# AUDIO.net
KiCad netlist of a schematic drawn in Altium Designer
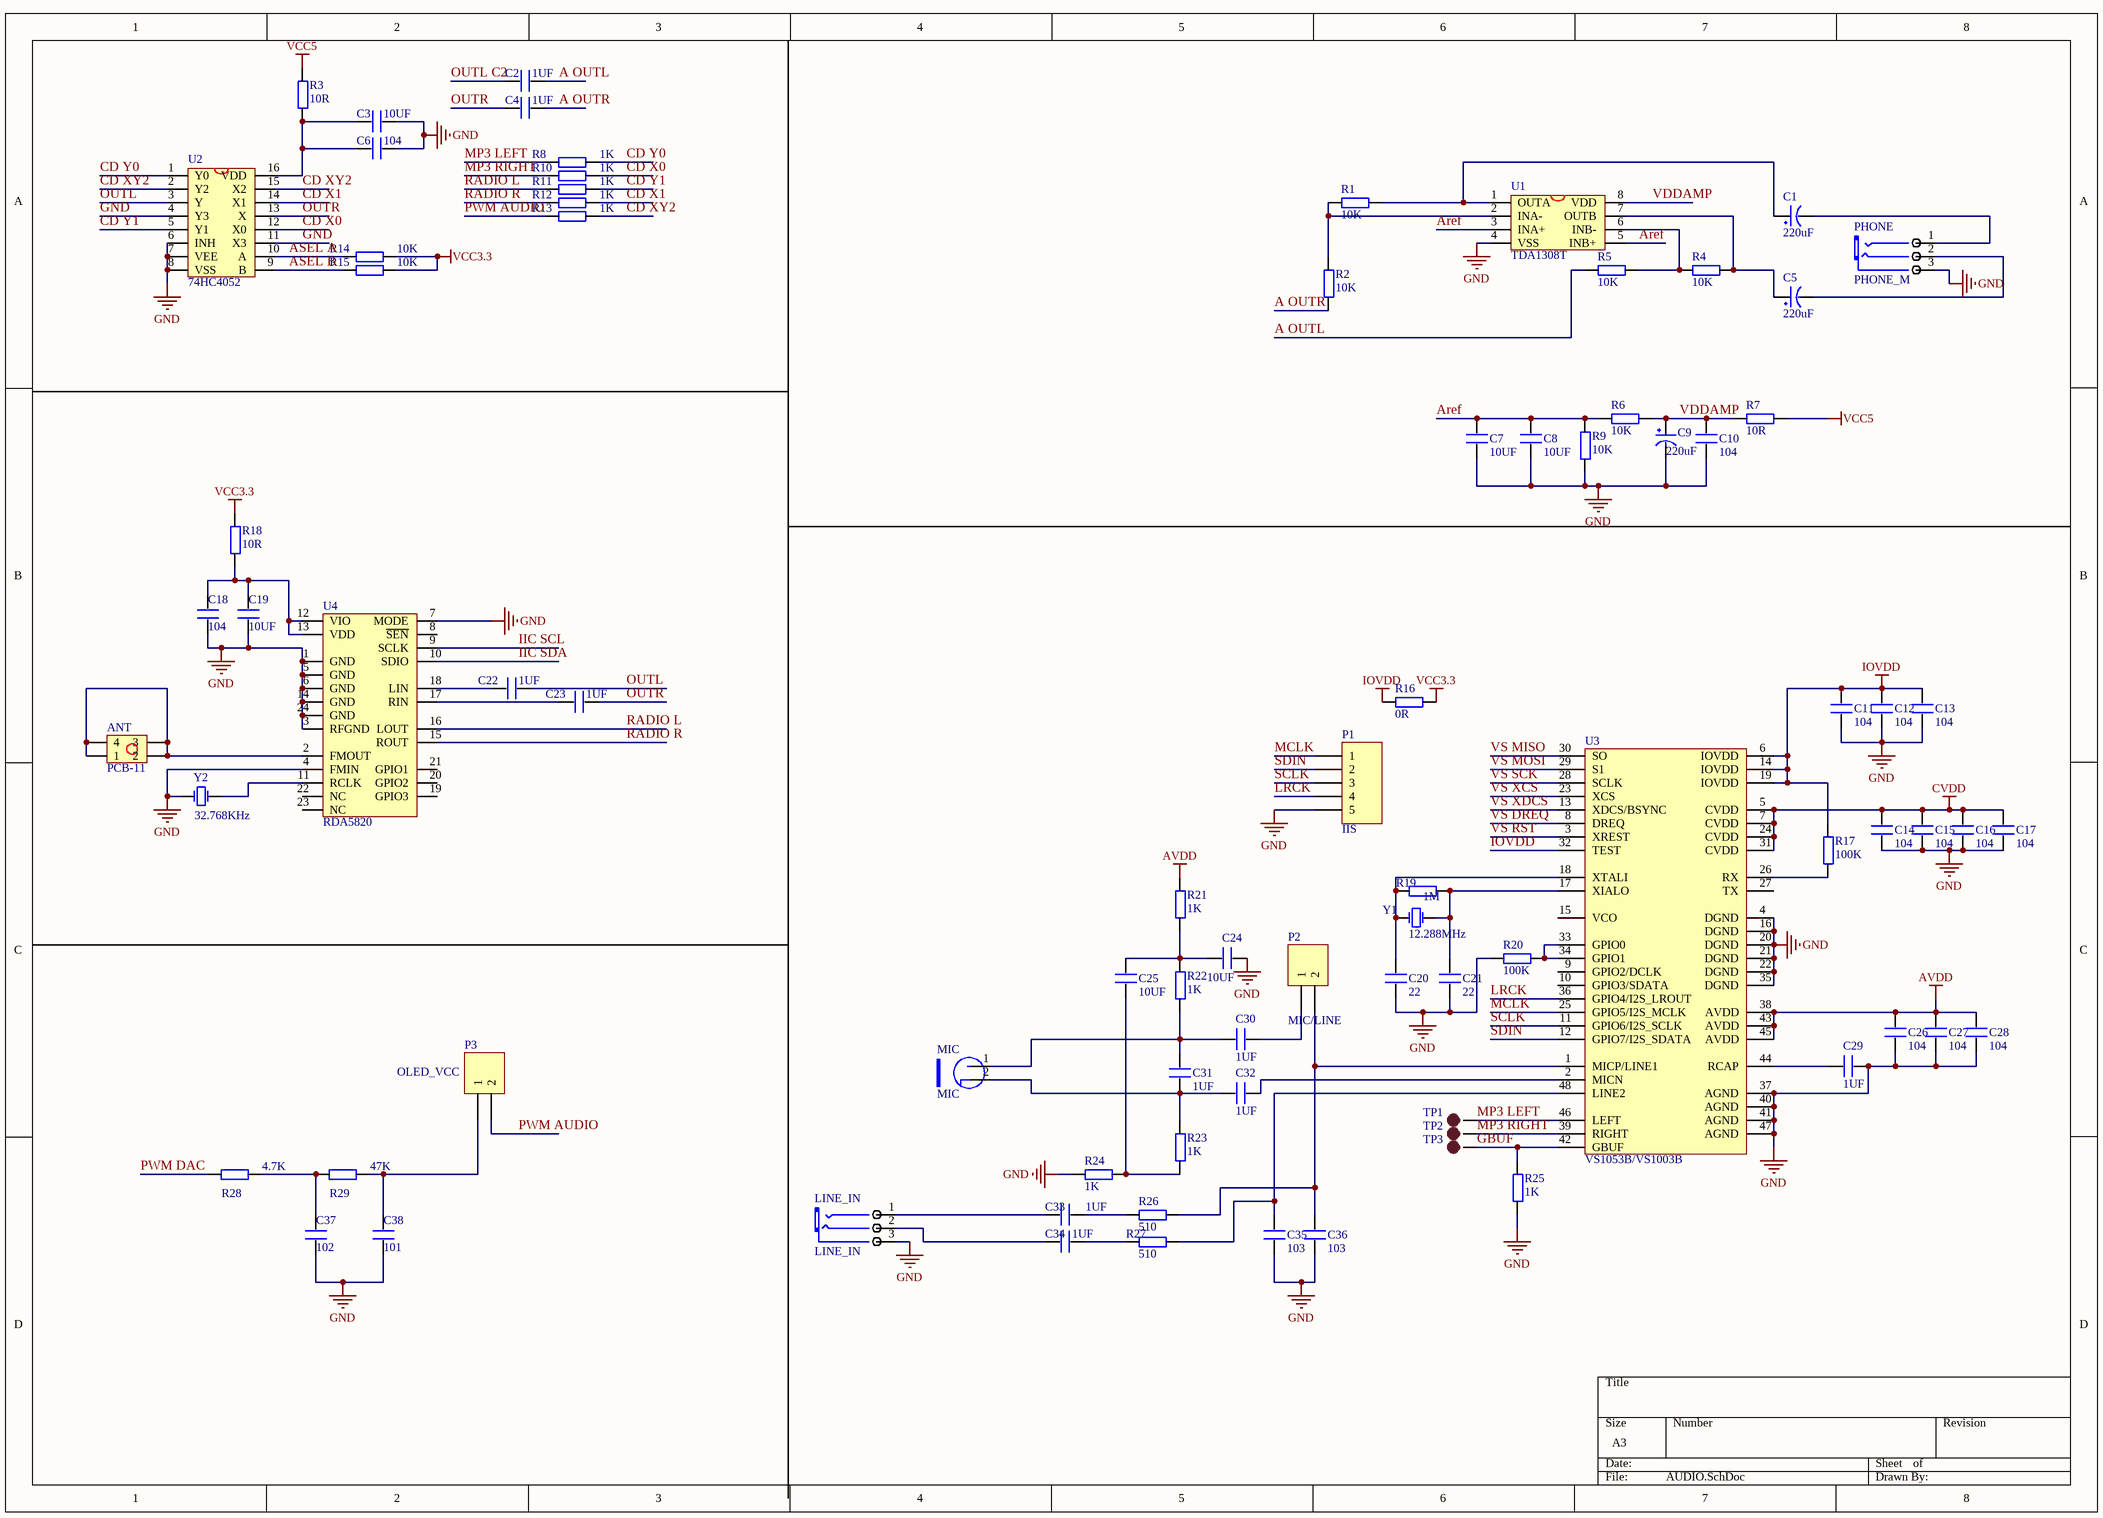
[diagram p0: AUDIO.SchDoc]

(export (version "E")
  (design (tool "Eeschema 10.0.6"))
  (components
    (comp (ref "ANT")
      (value "PCB-11")
      (footprint "PCB-11")
      (description "PCB接线端子")
      (libsource (lib "战舰STM32开发板底板封装库") (part "PCB-11"))
    )
    (comp (ref "C1") (value "220uF") (footprint "CC6.56.5") (libsource (lib "战舰STM32开发板底板封装库") (part "CAP")))
    (comp (ref "C2") (value "1UF") (footprint "0603P") (libsource (lib "战舰STM32开发板底板封装库") (part "C")))
    (comp (ref "C3") (value "10UF") (footprint "0603P") (libsource (lib "战舰STM32开发板底板封装库") (part "C")))
    (comp (ref "C4") (value "1UF") (footprint "0603P") (libsource (lib "战舰STM32开发板底板封装库") (part "C")))
    (comp (ref "C5") (value "220uF") (footprint "CC6.56.5") (libsource (lib "战舰STM32开发板底板封装库") (part "CAP")))
    (comp (ref "C6") (value "104") (footprint "0603P") (libsource (lib "战舰STM32开发板底板封装库") (part "C")))
    (comp (ref "C7") (value "10UF") (footprint "0603P") (libsource (lib "战舰STM32开发板底板封装库") (part "C")))
    (comp (ref "C8") (value "10UF") (footprint "0603P") (libsource (lib "战舰STM32开发板底板封装库") (part "C")))
    (comp (ref "C9") (value "220uF") (footprint "CC6.56.5") (libsource (lib "") (part "CAP_1")))
    (comp (ref "C10") (value "104") (footprint "0603P") (libsource (lib "战舰STM32开发板底板封装库") (part "C")))
    (comp (ref "C11") (value "104") (footprint "0603P") (libsource (lib "战舰STM32开发板底板封装库") (part "C")))
    (comp (ref "C12") (value "104") (footprint "0603P") (libsource (lib "战舰STM32开发板底板封装库") (part "C")))
    (comp (ref "C13") (value "104") (footprint "0603P") (libsource (lib "战舰STM32开发板底板封装库") (part "C")))
    (comp (ref "C14") (value "104") (footprint "0603P") (libsource (lib "战舰STM32开发板底板封装库") (part "C")))
    (comp (ref "C15") (value "104") (footprint "0603P") (libsource (lib "战舰STM32开发板底板封装库") (part "C")))
    (comp (ref "C16") (value "104") (footprint "0603P") (libsource (lib "战舰STM32开发板底板封装库") (part "C")))
    (comp (ref "C17") (value "104") (footprint "0603P") (libsource (lib "战舰STM32开发板底板封装库") (part "C")))
    (comp (ref "C18") (value "104") (footprint "0603P") (libsource (lib "战舰STM32开发板底板封装库") (part "C")))
    (comp (ref "C19") (value "10UF") (footprint "0603P") (libsource (lib "战舰STM32开发板底板封装库") (part "C")))
    (comp (ref "C20") (value "22") (footprint "0603P") (libsource (lib "战舰STM32开发板底板封装库") (part "C")))
    (comp (ref "C21") (value "22") (footprint "0603P") (libsource (lib "战舰STM32开发板底板封装库") (part "C")))
    (comp (ref "C22") (value "1UF") (footprint "0603P") (libsource (lib "战舰STM32开发板底板封装库") (part "C")))
    (comp (ref "C23") (value "1UF") (footprint "0603P") (libsource (lib "战舰STM32开发板底板封装库") (part "C")))
    (comp (ref "C24") (value "10UF") (footprint "0603P") (libsource (lib "战舰STM32开发板底板封装库") (part "C")))
    (comp (ref "C25") (value "10UF") (footprint "0603P") (libsource (lib "战舰STM32开发板底板封装库") (part "C")))
    (comp (ref "C26") (value "104") (footprint "0603P") (libsource (lib "战舰STM32开发板底板封装库") (part "C")))
    (comp (ref "C27") (value "104") (footprint "0603P") (libsource (lib "战舰STM32开发板底板封装库") (part "C")))
    (comp (ref "C28") (value "104") (footprint "0603P") (libsource (lib "战舰STM32开发板底板封装库") (part "C")))
    (comp (ref "C29") (value "1UF") (footprint "0603P") (libsource (lib "战舰STM32开发板底板封装库") (part "C")))
    (comp (ref "C30") (value "1UF") (footprint "0603P") (libsource (lib "战舰STM32开发板底板封装库") (part "C")))
    (comp (ref "C31") (value "1UF") (footprint "0603P") (libsource (lib "战舰STM32开发板底板封装库") (part "C")))
    (comp (ref "C32") (value "1UF") (footprint "0603P") (libsource (lib "战舰STM32开发板底板封装库") (part "C")))
    (comp (ref "C33") (value "1UF") (footprint "0603P") (libsource (lib "战舰STM32开发板底板封装库") (part "C")))
    (comp (ref "C34") (value "1UF") (footprint "0603P") (libsource (lib "战舰STM32开发板底板封装库") (part "C")))
    (comp (ref "C35") (value "103") (footprint "0603P") (libsource (lib "战舰STM32开发板底板封装库") (part "C")))
    (comp (ref "C36") (value "103") (footprint "0603P") (libsource (lib "战舰STM32开发板底板封装库") (part "C")))
    (comp (ref "C37") (value "102") (footprint "0603P") (libsource (lib "战舰STM32开发板底板封装库") (part "C")))
    (comp (ref "C38") (value "101") (footprint "0603P") (libsource (lib "战舰STM32开发板底板封装库") (part "C")))
    (comp (ref "LINE_IN")
      (value "LINE_IN")
      (footprint "PHONE_ST")
      (libsource (lib "战舰STM32开发板底板封装库") (part "PHONE_M"))
    )
    (comp (ref "MIC") (value "MIC") (footprint "MIC") (libsource (lib "战舰STM32开发板底板封装库") (part "MIC")))
    (comp (ref "P1")
      (value "IIS")
      (footprint "HDR1X5")
      (description "Header, 5-Pin")
      (fields (field (name "PUBLISHER") "Altium Limited"))
      (libsource (lib "战舰STM32开发板底板封装库") (part "Header 5"))
    )
    (comp (ref "P2")
      (value "MIC/LINE")
      (footprint "HDR1X2")
      (description "Header, 2-Pin")
      (fields (field (name "PUBLISHER") "Altium Limited"))
      (libsource (lib "战舰STM32开发板底板封装库") (part "Header 2"))
    )
    (comp (ref "P3")
      (value "OLED_VCC")
      (footprint "HDR1X2")
      (description "Header, 2-Pin")
      (fields (field (name "PUBLISHER") "Altium Limited"))
      (libsource (lib "战舰STM32开发板底板封装库") (part "Header 2"))
    )
    (comp (ref "PHONE")
      (value "PHONE_M")
      (footprint "PHONE_ST")
      (libsource (lib "战舰STM32开发板底板封装库") (part "PHONE_M"))
    )
    (comp (ref "R1") (value "10K") (footprint "0603P") (libsource (lib "战舰STM32开发板底板封装库") (part "R")))
    (comp (ref "R2") (value "10K") (footprint "0603P") (libsource (lib "战舰STM32开发板底板封装库") (part "R")))
    (comp (ref "R3") (value "10R") (footprint "0603P") (libsource (lib "战舰STM32开发板底板封装库") (part "R")))
    (comp (ref "R4") (value "10K") (footprint "0603P") (libsource (lib "战舰STM32开发板底板封装库") (part "R")))
    (comp (ref "R5") (value "10K") (footprint "0603P") (libsource (lib "战舰STM32开发板底板封装库") (part "R")))
    (comp (ref "R6") (value "10K") (footprint "0603P") (libsource (lib "战舰STM32开发板底板封装库") (part "R")))
    (comp (ref "R7") (value "10R") (footprint "0603P") (libsource (lib "战舰STM32开发板底板封装库") (part "R")))
    (comp (ref "R8") (value "1K") (footprint "0603P") (libsource (lib "战舰STM32开发板底板封装库") (part "R")))
    (comp (ref "R9") (value "10K") (footprint "0603P") (libsource (lib "战舰STM32开发板底板封装库") (part "R")))
    (comp (ref "R10") (value "1K") (footprint "0603P") (libsource (lib "战舰STM32开发板底板封装库") (part "R")))
    (comp (ref "R11") (value "1K") (footprint "0603P") (libsource (lib "战舰STM32开发板底板封装库") (part "R")))
    (comp (ref "R12") (value "1K") (footprint "0603P") (libsource (lib "战舰STM32开发板底板封装库") (part "R")))
    (comp (ref "R13") (value "1K") (footprint "0603P") (libsource (lib "战舰STM32开发板底板封装库") (part "R")))
    (comp (ref "R14") (value "10K") (footprint "0603P") (libsource (lib "战舰STM32开发板底板封装库") (part "R")))
    (comp (ref "R15") (value "10K") (footprint "0603P") (libsource (lib "战舰STM32开发板底板封装库") (part "R")))
    (comp (ref "R16") (value "0R") (footprint "0603P") (libsource (lib "战舰STM32开发板底板封装库") (part "R")))
    (comp (ref "R17") (value "100K") (footprint "0603P") (libsource (lib "战舰STM32开发板底板封装库") (part "R")))
    (comp (ref "R18") (value "10R") (footprint "0603P") (libsource (lib "战舰STM32开发板底板封装库") (part "R")))
    (comp (ref "R19") (value "1M") (footprint "0603P") (libsource (lib "战舰STM32开发板底板封装库") (part "R")))
    (comp (ref "R20") (value "100K") (footprint "0603P") (libsource (lib "战舰STM32开发板底板封装库") (part "R")))
    (comp (ref "R21") (value "1K") (footprint "0603P") (libsource (lib "战舰STM32开发板底板封装库") (part "R")))
    (comp (ref "R22") (value "1K") (footprint "0603P") (libsource (lib "战舰STM32开发板底板封装库") (part "R")))
    (comp (ref "R23") (value "1K") (footprint "0603P") (libsource (lib "战舰STM32开发板底板封装库") (part "R")))
    (comp (ref "R24") (value "1K") (footprint "0603P") (libsource (lib "战舰STM32开发板底板封装库") (part "R")))
    (comp (ref "R25") (value "1K") (footprint "0603P") (libsource (lib "战舰STM32开发板底板封装库") (part "R")))
    (comp (ref "R26") (value "510") (footprint "0603P") (libsource (lib "战舰STM32开发板底板封装库") (part "R")))
    (comp (ref "R27") (value "510") (footprint "0603P") (libsource (lib "战舰STM32开发板底板封装库") (part "R")))
    (comp (ref "R28") (value "4.7K") (footprint "0603P") (libsource (lib "战舰STM32开发板底板封装库") (part "R")))
    (comp (ref "R29") (value "47K") (footprint "0603P") (libsource (lib "战舰STM32开发板底板封装库") (part "R")))
    (comp (ref "TP1")
      (value "TEST POINT")
      (footprint "TP-1.5")
      (description "测试点")
      (libsource (lib "战舰STM32开发板底板封装库") (part "TEST-POINT"))
    )
    (comp (ref "TP2")
      (value "TEST POINT")
      (footprint "TP-1.5")
      (description "测试点")
      (libsource (lib "战舰STM32开发板底板封装库") (part "TEST-POINT"))
    )
    (comp (ref "TP3")
      (value "TEST POINT")
      (footprint "TP-1.5")
      (description "测试点")
      (libsource (lib "战舰STM32开发板底板封装库") (part "TEST-POINT"))
    )
    (comp (ref "U1")
      (value "TDA1308T")
      (footprint "SOP-8")
      (libsource (lib "战舰STM32开发板底板封装库") (part "TDA1308"))
    )
    (comp (ref "U2")
      (value "74HC4052")
      (footprint "SOP16M")
      (libsource (lib "战舰STM32开发板底板封装库") (part "CD4052"))
    )
    (comp (ref "U3")
      (value "VS1053B/VS1003B")
      (footprint "mTQFP48")
      (libsource (lib "战舰STM32开发板底板封装库") (part "VS1053"))
    )
    (comp (ref "U4")
      (value "RDA5820")
      (footprint "QFN24")
      (libsource (lib "战舰STM32开发板底板封装库") (part "RDA5820"))
    )
    (comp (ref "Y1")
      (value "12.288MHz")
      (footprint "XTAL_US")
      (description "Crystal Oscillator")
      (fields (field (name "PUBLISHER") "Altium Limited"))
      (libsource (lib "战舰STM32开发板底板封装库") (part "XTAL_2"))
    )
    (comp (ref "Y2")
      (value "32.768KHz")
      (footprint "XTAL32")
      (description "32.768K")
      (fields (field (name "PUBLISHER") "Altium Limited"))
      (libsource (lib "战舰STM32开发板底板封装库") (part "XTAL_3"))
    )
  )
  (nets
    (net (code "1") (name "/A OUTL") (class "Default")
      (node (ref "C2") (pin "2") (pintype "passive"))
      (node (ref "R5") (pin "1") (pintype "passive"))
    )
    (net (code "2") (name "/A OUTR") (class "Default")
      (node (ref "C4") (pin "2") (pintype "passive"))
      (node (ref "R2") (pin "1") (pintype "passive"))
    )
    (net (code "3") (name "/ASEL A") (class "Default")
      (node (ref "R14") (pin "1") (pintype "passive"))
      (node (ref "U2") (pin "10") (pinfunction "A_10") (pintype "passive"))
    )
    (net (code "4") (name "/ASEL B") (class "Default")
      (node (ref "R15") (pin "1") (pintype "passive"))
      (node (ref "U2") (pin "9") (pinfunction "B_9") (pintype "passive"))
    )
    (net (code "5") (name "/Aref") (class "Default")
      (node (ref "C7") (pin "2") (pintype "passive"))
      (node (ref "C8") (pin "2") (pintype "passive"))
      (node (ref "R6") (pin "1") (pintype "passive"))
      (node (ref "R9") (pin "2") (pintype "passive"))
      (node (ref "U1") (pin "3") (pinfunction "INA+_3") (pintype "passive"))
      (node (ref "U1") (pin "5") (pinfunction "INB+_5") (pintype "passive"))
    )
    (net (code "6") (name "/CD X0") (class "Default")
      (node (ref "R10") (pin "2") (pintype "passive"))
      (node (ref "U2") (pin "12") (pinfunction "X0_12") (pintype "passive"))
    )
    (net (code "7") (name "/CD X1") (class "Default")
      (node (ref "R12") (pin "2") (pintype "passive"))
      (node (ref "U2") (pin "14") (pinfunction "X1_14") (pintype "passive"))
    )
    (net (code "8") (name "/CD XY2") (class "Default")
      (node (ref "R13") (pin "2") (pintype "passive"))
      (node (ref "U2") (pin "15") (pinfunction "X2_15") (pintype "passive"))
      (node (ref "U2") (pin "2") (pinfunction "Y2_2") (pintype "passive"))
    )
    (net (code "9") (name "/CD Y0") (class "Default")
      (node (ref "R8") (pin "2") (pintype "passive"))
      (node (ref "U2") (pin "1") (pinfunction "Y0_1") (pintype "passive"))
    )
    (net (code "10") (name "/CD Y1") (class "Default")
      (node (ref "R11") (pin "2") (pintype "passive"))
      (node (ref "U2") (pin "5") (pinfunction "Y1_5") (pintype "passive"))
    )
    (net (code "11") (name "/GBUF") (class "Default")
      (node (ref "R25") (pin "2") (pintype "passive"))
      (node (ref "TP3") (pin "1") (pinfunction "1_1") (pintype "passive"))
      (node (ref "U3") (pin "42") (pinfunction "GBUF_42") (pintype "passive"))
    )
    (net (code "12") (name "/IIC SCL") (class "Default")
      (node (ref "U4") (pin "9") (pinfunction "SCLK_9") (pintype "passive"))
    )
    (net (code "13") (name "/IIC SDA") (class "Default")
      (node (ref "U4") (pin "10") (pinfunction "SDIO_10") (pintype "passive"))
    )
    (net (code "14") (name "/LRCK") (class "Default")
      (node (ref "P1") (pin "4") (pinfunction "4_4") (pintype "passive"))
      (node (ref "U3") (pin "36") (pinfunction "GPIO4/I2S_LROUT_36") (pintype "passive"))
    )
    (net (code "15") (name "/MCLK") (class "Default")
      (node (ref "P1") (pin "1") (pinfunction "1_1") (pintype "passive"))
      (node (ref "U3") (pin "25") (pinfunction "GPIO5/I2S_MCLK_25") (pintype "passive"))
    )
    (net (code "16") (name "/MP3 LEFT") (class "Default")
      (node (ref "R8") (pin "1") (pintype "passive"))
      (node (ref "TP1") (pin "1") (pinfunction "1_1") (pintype "passive"))
      (node (ref "U3") (pin "46") (pinfunction "LEFT_46") (pintype "passive"))
    )
    (net (code "17") (name "/MP3 RIGHT") (class "Default")
      (node (ref "R10") (pin "1") (pintype "passive"))
      (node (ref "TP2") (pin "1") (pinfunction "1_1") (pintype "passive"))
      (node (ref "U3") (pin "39") (pinfunction "RIGHT_39") (pintype "passive"))
    )
    (net (code "18") (name "/OUTL") (class "Default")
      (node (ref "C22") (pin "1") (pintype "passive"))
      (node (ref "U2") (pin "3") (pinfunction "Y_3") (pintype "passive"))
    )
    (net (code "19") (name "/OUTL C2") (class "Default") (node (ref "C2") (pin "1") (pintype "passive")))
    (net (code "20") (name "/OUTR") (class "Default")
      (node (ref "C23") (pin "1") (pintype "passive"))
      (node (ref "C4") (pin "1") (pintype "passive"))
      (node (ref "U2") (pin "13") (pinfunction "X_13") (pintype "passive"))
    )
    (net (code "21") (name "/PWM AUDIO") (class "Default")
      (node (ref "P3") (pin "2") (pinfunction "2_2") (pintype "passive"))
      (node (ref "R13") (pin "1") (pintype "passive"))
    )
    (net (code "22") (name "/PWM DAC") (class "Default") (node (ref "R28") (pin "1") (pintype "passive")))
    (net (code "23") (name "/RADIO L") (class "Default")
      (node (ref "R11") (pin "1") (pintype "passive"))
      (node (ref "U4") (pin "16") (pinfunction "LOUT_16") (pintype "passive"))
    )
    (net (code "24") (name "/RADIO R") (class "Default")
      (node (ref "R12") (pin "1") (pintype "passive"))
      (node (ref "U4") (pin "15") (pinfunction "ROUT_15") (pintype "passive"))
    )
    (net (code "25") (name "/SCLK") (class "Default")
      (node (ref "P1") (pin "3") (pinfunction "3_3") (pintype "passive"))
      (node (ref "U3") (pin "11") (pinfunction "GPIO6/I2S_SCLK_11") (pintype "passive"))
    )
    (net (code "26") (name "/SDIN") (class "Default")
      (node (ref "P1") (pin "2") (pinfunction "2_2") (pintype "passive"))
      (node (ref "U3") (pin "12") (pinfunction "GPIO7/I2S_SDATA_12") (pintype "passive"))
    )
    (net (code "27") (name "/VDDAMP") (class "Default")
      (node (ref "C10") (pin "2") (pintype "passive"))
      (node (ref "C9") (pin "1") (pinfunction "VCC_1") (pintype "passive"))
      (node (ref "R6") (pin "2") (pintype "passive"))
      (node (ref "R7") (pin "1") (pintype "passive"))
      (node (ref "U1") (pin "8") (pinfunction "VDD_8") (pintype "passive"))
    )
    (net (code "28") (name "/VS DREQ") (class "Default")
      (node (ref "U3") (pin "8") (pinfunction "DREQ_8") (pintype "passive"))
    )
    (net (code "29") (name "/VS MISO") (class "Default")
      (node (ref "U3") (pin "30") (pinfunction "SO_30") (pintype "passive"))
    )
    (net (code "30") (name "/VS MOSI") (class "Default")
      (node (ref "U3") (pin "29") (pinfunction "S1_29") (pintype "passive"))
    )
    (net (code "31") (name "/VS RST") (class "Default")
      (node (ref "U3") (pin "3") (pinfunction "XREST_3") (pintype "passive"))
    )
    (net (code "32") (name "/VS SCK") (class "Default")
      (node (ref "U3") (pin "28") (pinfunction "SCLK_28") (pintype "passive"))
    )
    (net (code "33") (name "/VS XCS") (class "Default")
      (node (ref "U3") (pin "23") (pinfunction "XCS_23") (pintype "passive"))
    )
    (net (code "34") (name "/VS XDCS") (class "Default")
      (node (ref "U3") (pin "13") (pinfunction "XDCS/BSYNC_13") (pintype "passive"))
    )
    (net (code "35") (name "AVDD") (class "Default")
      (node (ref "C26") (pin "2") (pintype "passive"))
      (node (ref "C27") (pin "2") (pintype "passive"))
      (node (ref "C28") (pin "2") (pintype "passive"))
      (node (ref "R21") (pin "2") (pintype "passive"))
      (node (ref "U3") (pin "38") (pinfunction "AVDD_38") (pintype "passive"))
      (node (ref "U3") (pin "43") (pinfunction "AVDD_43") (pintype "passive"))
      (node (ref "U3") (pin "45") (pinfunction "AVDD_45") (pintype "passive"))
    )
    (net (code "36") (name "CVDD") (class "Default")
      (node (ref "C14") (pin "2") (pintype "passive"))
      (node (ref "C15") (pin "2") (pintype "passive"))
      (node (ref "C16") (pin "2") (pintype "passive"))
      (node (ref "C17") (pin "2") (pintype "passive"))
      (node (ref "U3") (pin "24") (pinfunction "CVDD_24") (pintype "passive"))
      (node (ref "U3") (pin "31") (pinfunction "CVDD_31") (pintype "passive"))
      (node (ref "U3") (pin "5") (pinfunction "CVDD_5") (pintype "passive"))
      (node (ref "U3") (pin "7") (pinfunction "CVDD_7") (pintype "passive"))
    )
    (net (code "37") (name "GND") (class "Default")
      (node (ref "C10") (pin "1") (pintype "passive"))
      (node (ref "C11") (pin "1") (pintype "passive"))
      (node (ref "C12") (pin "1") (pintype "passive"))
      (node (ref "C13") (pin "1") (pintype "passive"))
      (node (ref "C14") (pin "1") (pintype "passive"))
      (node (ref "C15") (pin "1") (pintype "passive"))
      (node (ref "C16") (pin "1") (pintype "passive"))
      (node (ref "C17") (pin "1") (pintype "passive"))
      (node (ref "C18") (pin "1") (pintype "passive"))
      (node (ref "C19") (pin "1") (pintype "passive"))
      (node (ref "C20") (pin "1") (pintype "passive"))
      (node (ref "C21") (pin "1") (pintype "passive"))
      (node (ref "C24") (pin "1") (pintype "passive"))
      (node (ref "C26") (pin "1") (pintype "passive"))
      (node (ref "C27") (pin "1") (pintype "passive"))
      (node (ref "C28") (pin "1") (pintype "passive"))
      (node (ref "C29") (pin "2") (pintype "passive"))
      (node (ref "C3") (pin "2") (pintype "passive"))
      (node (ref "C35") (pin "1") (pintype "passive"))
      (node (ref "C36") (pin "1") (pintype "passive"))
      (node (ref "C37") (pin "1") (pintype "passive"))
      (node (ref "C38") (pin "1") (pintype "passive"))
      (node (ref "C6") (pin "2") (pintype "passive"))
      (node (ref "C7") (pin "1") (pintype "passive"))
      (node (ref "C8") (pin "1") (pintype "passive"))
      (node (ref "C9") (pin "2") (pinfunction "GND_2") (pintype "passive"))
      (node (ref "LINE_IN") (pin "3") (pinfunction "COM_3") (pintype "passive"))
      (node (ref "P1") (pin "5") (pinfunction "5_5") (pintype "passive"))
      (node (ref "PHONE") (pin "3") (pinfunction "COM_3") (pintype "passive"))
      (node (ref "R20") (pin "1") (pintype "passive"))
      (node (ref "R24") (pin "1") (pintype "passive"))
      (node (ref "R25") (pin "1") (pintype "passive"))
      (node (ref "R9") (pin "1") (pintype "passive"))
      (node (ref "U1") (pin "4") (pinfunction "VSS_4") (pintype "passive"))
      (node (ref "U2") (pin "11") (pinfunction "X3_11") (pintype "passive"))
      (node (ref "U2") (pin "4") (pinfunction "Y3_4") (pintype "passive"))
      (node (ref "U2") (pin "6") (pinfunction "INH_6") (pintype "passive"))
      (node (ref "U2") (pin "7") (pinfunction "VEE_7") (pintype "passive"))
      (node (ref "U2") (pin "8") (pinfunction "VSS_8") (pintype "passive"))
      (node (ref "U3") (pin "16") (pinfunction "DGND_16") (pintype "passive"))
      (node (ref "U3") (pin "20") (pinfunction "DGND_20") (pintype "passive"))
      (node (ref "U3") (pin "21") (pinfunction "DGND_21") (pintype "passive"))
      (node (ref "U3") (pin "22") (pinfunction "DGND_22") (pintype "passive"))
      (node (ref "U3") (pin "35") (pinfunction "DGND_35") (pintype "passive"))
      (node (ref "U3") (pin "37") (pinfunction "AGND_37") (pintype "passive"))
      (node (ref "U3") (pin "4") (pinfunction "DGND_4") (pintype "passive"))
      (node (ref "U3") (pin "40") (pinfunction "AGND_40") (pintype "passive"))
      (node (ref "U3") (pin "41") (pinfunction "AGND_41") (pintype "passive"))
      (node (ref "U3") (pin "47") (pinfunction "AGND_47") (pintype "passive"))
      (node (ref "U4") (pin "1") (pinfunction "GND_1") (pintype "passive"))
      (node (ref "U4") (pin "14") (pinfunction "GND_14") (pintype "passive"))
      (node (ref "U4") (pin "24") (pinfunction "GND_24") (pintype "passive"))
      (node (ref "U4") (pin "3") (pinfunction "RFGND_3") (pintype "passive"))
      (node (ref "U4") (pin "4") (pinfunction "FMIN_4") (pintype "passive"))
      (node (ref "U4") (pin "5") (pinfunction "GND_5") (pintype "passive"))
      (node (ref "U4") (pin "6") (pinfunction "GND_6") (pintype "passive"))
      (node (ref "U4") (pin "7") (pinfunction "MODE_7") (pintype "passive"))
      (node (ref "Y2") (pin "1") (pinfunction "OSC1_1") (pintype "passive"))
    )
    (net (code "38") (name "IOVDD") (class "Default")
      (node (ref "C11") (pin "2") (pintype "passive"))
      (node (ref "C12") (pin "2") (pintype "passive"))
      (node (ref "C13") (pin "2") (pintype "passive"))
      (node (ref "R16") (pin "1") (pintype "passive"))
      (node (ref "R17") (pin "2") (pintype "passive"))
      (node (ref "U3") (pin "14") (pinfunction "IOVDD_14") (pintype "passive"))
      (node (ref "U3") (pin "19") (pinfunction "IOVDD_19") (pintype "passive"))
      (node (ref "U3") (pin "32") (pinfunction "TEST_32") (pintype "passive"))
      (node (ref "U3") (pin "6") (pinfunction "IOVDD_6") (pintype "passive"))
    )
    (net (code "39") (name "Net-(C1-GND)") (class "Default")
      (node (ref "C1") (pin "2") (pinfunction "GND_2") (pintype "passive"))
      (node (ref "PHONE") (pin "1") (pinfunction "CHL_1") (pintype "passive"))
    )
    (net (code "40") (name "Net-(C1-VCC)") (class "Default")
      (node (ref "C1") (pin "1") (pinfunction "VCC_1") (pintype "passive"))
      (node (ref "R1") (pin "2") (pintype "passive"))
      (node (ref "U1") (pin "1") (pinfunction "OUTA_1") (pintype "passive"))
    )
    (net (code "41") (name "Net-(C5-GND)") (class "Default")
      (node (ref "C5") (pin "2") (pinfunction "GND_2") (pintype "passive"))
      (node (ref "PHONE") (pin "2") (pinfunction "CHR_2") (pintype "passive"))
    )
    (net (code "42") (name "Net-(C5-VCC)") (class "Default")
      (node (ref "C5") (pin "1") (pinfunction "VCC_1") (pintype "passive"))
      (node (ref "R4") (pin "2") (pintype "passive"))
      (node (ref "U1") (pin "7") (pinfunction "OUTB_7") (pintype "passive"))
    )
    (net (code "43") (name "Net-(C24-Pad2)") (class "Default")
      (node (ref "C24") (pin "2") (pintype "passive"))
      (node (ref "C25") (pin "2") (pintype "passive"))
      (node (ref "R21") (pin "1") (pintype "passive"))
      (node (ref "R22") (pin "2") (pintype "passive"))
    )
    (net (code "44") (name "Net-(C25-Pad1)") (class "Default")
      (node (ref "C25") (pin "1") (pintype "passive"))
      (node (ref "R23") (pin "1") (pintype "passive"))
      (node (ref "R24") (pin "2") (pintype "passive"))
    )
    (net (code "45") (name "Net-(C30-Pad2)") (class "Default")
      (node (ref "C30") (pin "2") (pintype "passive"))
      (node (ref "P2") (pin "1") (pinfunction "1_1") (pintype "passive"))
    )
    (net (code "46") (name "Net-(C33-Pad2)") (class "Default")
      (node (ref "C33") (pin "2") (pintype "passive"))
      (node (ref "R26") (pin "1") (pintype "passive"))
    )
    (net (code "47") (name "Net-(C34-Pad2)") (class "Default")
      (node (ref "C34") (pin "2") (pintype "passive"))
      (node (ref "R27") (pin "1") (pintype "passive"))
    )
    (net (code "48") (name "Net-(C37-Pad2)") (class "Default")
      (node (ref "C37") (pin "2") (pintype "passive"))
      (node (ref "R28") (pin "2") (pintype "passive"))
      (node (ref "R29") (pin "1") (pintype "passive"))
    )
    (net (code "49") (name "Net-(C38-Pad2)") (class "Default")
      (node (ref "C38") (pin "2") (pintype "passive"))
      (node (ref "P3") (pin "1") (pinfunction "1_1") (pintype "passive"))
      (node (ref "R29") (pin "2") (pintype "passive"))
    )
    (net (code "50") (name "Net-(LINE_IN-CHL)") (class "Default")
      (node (ref "C33") (pin "1") (pintype "passive"))
      (node (ref "LINE_IN") (pin "1") (pinfunction "CHL_1") (pintype "passive"))
    )
    (net (code "51") (name "Net-(LINE_IN-CHR)") (class "Default")
      (node (ref "C34") (pin "1") (pintype "passive"))
      (node (ref "LINE_IN") (pin "2") (pinfunction "CHR_2") (pintype "passive"))
    )
    (net (code "52") (name "Net-(MIC-GND)") (class "Default")
      (node (ref "C31") (pin "1") (pintype "passive"))
      (node (ref "C32") (pin "1") (pintype "passive"))
      (node (ref "MIC") (pin "2") (pinfunction "GND_2") (pintype "passive"))
      (node (ref "R23") (pin "2") (pintype "passive"))
    )
    (net (code "53") (name "Net-(MIC-VCC)") (class "Default")
      (node (ref "C30") (pin "1") (pintype "passive"))
      (node (ref "C31") (pin "2") (pintype "passive"))
      (node (ref "MIC") (pin "1") (pinfunction "VCC_1") (pintype "passive"))
      (node (ref "R22") (pin "1") (pintype "passive"))
    )
    (net (code "54") (name "Net-(U1-INA-)") (class "Default")
      (node (ref "R1") (pin "1") (pintype "passive"))
      (node (ref "R2") (pin "2") (pintype "passive"))
      (node (ref "U1") (pin "2") (pinfunction "INA-_2") (pintype "passive"))
    )
    (net (code "55") (name "Net-(U1-INB-)") (class "Default")
      (node (ref "R4") (pin "1") (pintype "passive"))
      (node (ref "R5") (pin "2") (pintype "passive"))
      (node (ref "U1") (pin "6") (pinfunction "INB-_6") (pintype "passive"))
    )
    (net (code "56") (name "Net-(U2-VDD)") (class "Default")
      (node (ref "C3") (pin "1") (pintype "passive"))
      (node (ref "C6") (pin "1") (pintype "passive"))
      (node (ref "R3") (pin "1") (pintype "passive"))
      (node (ref "U2") (pin "16") (pinfunction "VDD_16") (pintype "passive"))
    )
    (net (code "57") (name "Net-(U3-GPIO0)") (class "Default")
      (node (ref "R20") (pin "2") (pintype "passive"))
      (node (ref "U3") (pin "33") (pinfunction "GPIO0_33") (pintype "passive"))
      (node (ref "U3") (pin "34") (pinfunction "GPIO1_34") (pintype "passive"))
    )
    (net (code "58") (name "Net-(U3-LINE2)") (class "Default")
      (node (ref "C35") (pin "2") (pintype "passive"))
      (node (ref "R27") (pin "2") (pintype "passive"))
      (node (ref "U3") (pin "48") (pinfunction "LINE2_48") (pintype "passive"))
    )
    (net (code "59") (name "Net-(U3-MICN)") (class "Default")
      (node (ref "C32") (pin "2") (pintype "passive"))
      (node (ref "U3") (pin "2") (pinfunction "MICN_2") (pintype "passive"))
    )
    (net (code "60") (name "Net-(U3-MICP{slash}LINE1)") (class "Default")
      (node (ref "C36") (pin "2") (pintype "passive"))
      (node (ref "P2") (pin "2") (pinfunction "2_2") (pintype "passive"))
      (node (ref "R26") (pin "2") (pintype "passive"))
      (node (ref "U3") (pin "1") (pinfunction "MICP/LINE1_1") (pintype "passive"))
    )
    (net (code "61") (name "Net-(U3-RCAP)") (class "Default")
      (node (ref "C29") (pin "1") (pintype "passive"))
      (node (ref "U3") (pin "44") (pinfunction "RCAP_44") (pintype "passive"))
    )
    (net (code "62") (name "Net-(U3-RX)") (class "Default")
      (node (ref "R17") (pin "1") (pintype "passive"))
      (node (ref "U3") (pin "26") (pinfunction "RX_26") (pintype "passive"))
    )
    (net (code "63") (name "Net-(U3-XIALO)") (class "Default")
      (node (ref "C21") (pin "2") (pintype "passive"))
      (node (ref "R19") (pin "2") (pintype "passive"))
      (node (ref "U3") (pin "17") (pinfunction "XIALO_17") (pintype "passive"))
      (node (ref "Y1") (pin "2") (pinfunction "OSC2_2") (pintype "passive"))
    )
    (net (code "64") (name "Net-(U3-XTALI)") (class "Default")
      (node (ref "C20") (pin "2") (pintype "passive"))
      (node (ref "R19") (pin "1") (pintype "passive"))
      (node (ref "U3") (pin "18") (pinfunction "XTALI_18") (pintype "passive"))
      (node (ref "Y1") (pin "1") (pinfunction "OSC1_1") (pintype "passive"))
    )
    (net (code "65") (name "Net-(U4-FMOUT)") (class "Default")
      (node (ref "ANT") (pin "1") (pinfunction "1_1") (pintype "passive"))
      (node (ref "ANT") (pin "2") (pinfunction "2_2") (pintype "passive"))
      (node (ref "ANT") (pin "3") (pinfunction "3_3") (pintype "passive"))
      (node (ref "ANT") (pin "4") (pinfunction "4_4") (pintype "passive"))
      (node (ref "U4") (pin "2") (pinfunction "FMOUT_2") (pintype "passive"))
    )
    (net (code "66") (name "Net-(U4-LIN)") (class "Default")
      (node (ref "C22") (pin "2") (pintype "passive"))
      (node (ref "U4") (pin "18") (pinfunction "LIN_18") (pintype "passive"))
    )
    (net (code "67") (name "Net-(U4-RCLK)") (class "Default")
      (node (ref "U4") (pin "11") (pinfunction "RCLK_11") (pintype "passive"))
      (node (ref "Y2") (pin "2") (pinfunction "OSC2_2") (pintype "passive"))
    )
    (net (code "68") (name "Net-(U4-RIN)") (class "Default")
      (node (ref "C23") (pin "2") (pintype "passive"))
      (node (ref "U4") (pin "17") (pinfunction "RIN_17") (pintype "passive"))
    )
    (net (code "69") (name "Net-(U4-VDD)") (class "Default")
      (node (ref "C18") (pin "2") (pintype "passive"))
      (node (ref "C19") (pin "2") (pintype "passive"))
      (node (ref "R18") (pin "1") (pintype "passive"))
      (node (ref "U4") (pin "12") (pinfunction "VIO_12") (pintype "passive"))
      (node (ref "U4") (pin "13") (pinfunction "VDD_13") (pintype "passive"))
    )
    (net (code "70") (name "VCC3.3") (class "Default")
      (node (ref "R14") (pin "2") (pintype "passive"))
      (node (ref "R15") (pin "2") (pintype "passive"))
      (node (ref "R16") (pin "2") (pintype "passive"))
      (node (ref "R18") (pin "2") (pintype "passive"))
    )
    (net (code "71") (name "VCC5") (class "Default")
      (node (ref "R3") (pin "2") (pintype "passive"))
      (node (ref "R7") (pin "2") (pintype "passive"))
    )
    (net (code "72") (name "unconnected-(U3-GPIO2{slash}DCLK-Pad9)") (class "Default")
      (node (ref "U3") (pin "9") (pinfunction "GPIO2/DCLK_9") (pintype "passive"))
    )
    (net (code "73") (name "unconnected-(U3-GPIO3{slash}SDATA-Pad10)") (class "Default")
      (node (ref "U3") (pin "10") (pinfunction "GPIO3/SDATA_10") (pintype "passive"))
    )
    (net (code "74") (name "unconnected-(U3-TX-Pad27)") (class "Default")
      (node (ref "U3") (pin "27") (pinfunction "TX_27") (pintype "passive"))
    )
    (net (code "75") (name "unconnected-(U3-VCO-Pad15)") (class "Default")
      (node (ref "U3") (pin "15") (pinfunction "VCO_15") (pintype "passive"))
    )
    (net (code "76") (name "unconnected-(U4-GPIO1-Pad21)") (class "Default")
      (node (ref "U4") (pin "21") (pinfunction "GPIO1_21") (pintype "passive"))
    )
    (net (code "77") (name "unconnected-(U4-GPIO2-Pad20)") (class "Default")
      (node (ref "U4") (pin "20") (pinfunction "GPIO2_20") (pintype "passive"))
    )
    (net (code "78") (name "unconnected-(U4-GPIO3-Pad19)") (class "Default")
      (node (ref "U4") (pin "19") (pinfunction "GPIO3_19") (pintype "passive"))
    )
    (net (code "79") (name "unconnected-(U4-NC-Pad22)") (class "Default")
      (node (ref "U4") (pin "22") (pinfunction "NC_22") (pintype "passive"))
    )
    (net (code "80") (name "unconnected-(U4-NC-Pad23)") (class "Default")
      (node (ref "U4") (pin "23") (pinfunction "NC_23") (pintype "passive"))
    )
    (net (code "81") (name "unconnected-(U4-~{SEN}-Pad8)") (class "Default")
      (node (ref "U4") (pin "8") (pinfunction "~{SEN}_8") (pintype "passive"))
    )
  )
)
